# Blinky_Schematic.net
KiCad netlist of a schematic drawn in EAGLE
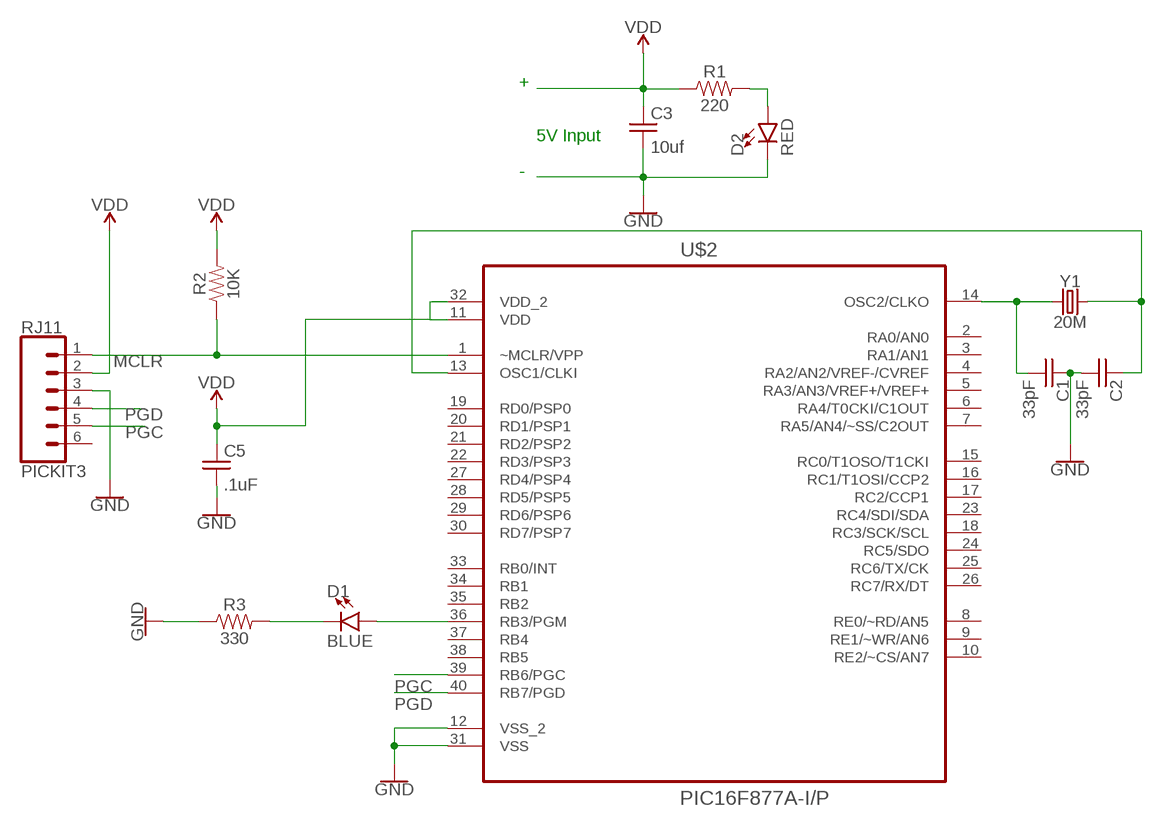
[diagram p0: schematic, sheet 1]

(export (version "E")
  (design (tool "Eeschema 10.0.6"))
  (components
    (comp (ref "C1")
      (value "33pF")
      (footprint "eagle-import:CAP_BULK")
      (fields (field (name "PARTNO") "EEE-FK1H220P"))
      (libsource (lib "eagle-import") (part "CAP_22UF_50VCAP_22UF_50V"))
    )
    (comp (ref "C2")
      (value "33pF")
      (footprint "eagle-import:CAP_BULK")
      (fields (field (name "PARTNO") "EEE-FK1H220P"))
      (libsource (lib "eagle-import") (part "CAP_22UF_50VCAP_22UF_50V"))
    )
    (comp (ref "C3")
      (value "10uf")
      (footprint "eagle-import:CAP_BULK")
      (fields (field (name "PARTNO") "EEE-FK1H220P"))
      (libsource (lib "eagle-import") (part "CAP_22UF_50VCAP_22UF_50V"))
    )
    (comp (ref "C5")
      (value ".1uF")
      (footprint "eagle-import:CAP_BULK")
      (fields (field (name "PARTNO") "EEE-FK1H220P"))
      (libsource (lib "eagle-import") (part "CAP_22UF_50VCAP_22UF_50V"))
    )
    (comp (ref "D1")
      (value "BLUE")
      (footprint "eagle-import:LED-0603")
      (libsource (lib "eagle-import") (part "LED-BLUE0603"))
    )
    (comp (ref "D2")
      (value "RED")
      (footprint "eagle-import:LED-0603")
      (libsource (lib "eagle-import") (part "LED-RED0603"))
    )
    (comp (ref "PICKIT3")
      (value "RJ11")
      (footprint "eagle-import:RJ11-6")
      (libsource (lib "eagle-import") (part "RJ11-6"))
    )
    (comp (ref "R1")
      (value "220")
      (footprint "eagle-import:0603")
      (libsource (lib "eagle-import") (part "1.2MOHM-0603-1/10W-1%"))
    )
    (comp (ref "R2")
      (value "10K")
      (footprint "eagle-import:0603")
      (libsource (lib "eagle-import") (part "1.2MOHM-0603-1/10W-1%"))
    )
    (comp (ref "R3")
      (value "330")
      (footprint "eagle-import:0603")
      (libsource (lib "eagle-import") (part "1.2MOHM-0603-1/10W-1%"))
    )
    (comp (ref "U$2")
      (value "PIC16F877A-I/P")
      (footprint "eagle-import:DIP254P1524X483-40")
      (libsource (lib "eagle-import") (part "PIC16F877A-I/P"))
    )
    (comp (ref "Y1")
      (value "20M")
      (footprint "eagle-import:CRYSTAL-PTH-2X6-CYL")
      (libsource (lib "eagle-import") (part "CRYSTALPTH-2X6"))
    )
  )
  (nets
    (net (code "1") (name "/MCLR") (class "Default")
      (node (ref "PICKIT3") (pin "1") (pinfunction "1_1") (pintype "passive"))
      (node (ref "R2") (pin "1") (pinfunction "1_1") (pintype "passive"))
      (node (ref "U$2") (pin "1") (pinfunction "~{MCLR/VPP}_1") (pintype "input"))
    )
    (net (code "2") (name "/PGC") (class "Default")
      (node (ref "PICKIT3") (pin "5") (pinfunction "5_5") (pintype "passive"))
      (node (ref "U$2") (pin "39") (pinfunction "RB6/PGC_39") (pintype "bidirectional"))
    )
    (net (code "3") (name "/PGD") (class "Default")
      (node (ref "PICKIT3") (pin "4") (pinfunction "4_4") (pintype "passive"))
      (node (ref "U$2") (pin "40") (pinfunction "RB7/PGD_40") (pintype "bidirectional"))
    )
    (net (code "4") (name "GND") (class "Default")
      (node (ref "C1") (pin "A") (pinfunction "+_A") (pintype "passive"))
      (node (ref "C2") (pin "B") (pinfunction "-_B") (pintype "passive"))
      (node (ref "C3") (pin "B") (pinfunction "-_B") (pintype "passive"))
      (node (ref "C5") (pin "B") (pinfunction "-_B") (pintype "passive"))
      (node (ref "D2") (pin "C") (pinfunction "C_C") (pintype "passive"))
      (node (ref "PICKIT3") (pin "3") (pinfunction "3_3") (pintype "passive"))
      (node (ref "R3") (pin "1") (pinfunction "1_1") (pintype "passive"))
      (node (ref "U$2") (pin "12") (pinfunction "VSS_2_12") (pintype "power_in"))
      (node (ref "U$2") (pin "31") (pinfunction "VSS_31") (pintype "power_in"))
    )
    (net (code "5") (name "Net-(C1--)") (class "Default")
      (node (ref "C1") (pin "B") (pinfunction "-_B") (pintype "passive"))
      (node (ref "U$2") (pin "14") (pinfunction "OSC2/CLKO_14") (pintype "output"))
      (node (ref "Y1") (pin "1") (pinfunction "1_1") (pintype "passive"))
    )
    (net (code "6") (name "Net-(C2-+)") (class "Default")
      (node (ref "C2") (pin "A") (pinfunction "+_A") (pintype "passive"))
      (node (ref "U$2") (pin "13") (pinfunction "OSC1/CLKI_13") (pintype "input"))
      (node (ref "Y1") (pin "2") (pinfunction "2_2") (pintype "passive"))
    )
    (net (code "7") (name "Net-(D1-PadC)") (class "Default")
      (node (ref "D1") (pin "C") (pinfunction "C_C") (pintype "passive"))
      (node (ref "R3") (pin "2") (pinfunction "2_2") (pintype "passive"))
    )
    (net (code "8") (name "Net-(D2-PadA)") (class "Default")
      (node (ref "D2") (pin "A") (pinfunction "A_A") (pintype "passive"))
      (node (ref "R1") (pin "2") (pinfunction "2_2") (pintype "passive"))
    )
    (net (code "9") (name "Net-(U$2-RB3{slash}PGM)") (class "Default")
      (node (ref "D1") (pin "A") (pinfunction "A_A") (pintype "passive"))
      (node (ref "U$2") (pin "36") (pinfunction "RB3/PGM_36") (pintype "bidirectional"))
    )
    (net (code "10") (name "VDD") (class "Default")
      (node (ref "C3") (pin "A") (pinfunction "+_A") (pintype "passive"))
      (node (ref "C5") (pin "A") (pinfunction "+_A") (pintype "passive"))
      (node (ref "PICKIT3") (pin "2") (pinfunction "2_2") (pintype "passive"))
      (node (ref "R1") (pin "1") (pinfunction "1_1") (pintype "passive"))
      (node (ref "R2") (pin "2") (pinfunction "2_2") (pintype "passive"))
      (node (ref "U$2") (pin "11") (pinfunction "VDD_11") (pintype "power_in"))
      (node (ref "U$2") (pin "32") (pinfunction "VDD_2_32") (pintype "power_in"))
    )
    (net (code "11") (name "unconnected-(PICKIT3-Pad6)") (class "Default")
      (node (ref "PICKIT3") (pin "6") (pinfunction "6_6") (pintype "passive"))
    )
    (net (code "12") (name "unconnected-(U$2-RA0{slash}AN0-Pad2)") (class "Default")
      (node (ref "U$2") (pin "2") (pinfunction "RA0/AN0_2") (pintype "bidirectional"))
    )
    (net (code "13") (name "unconnected-(U$2-RA1{slash}AN1-Pad3)") (class "Default")
      (node (ref "U$2") (pin "3") (pinfunction "RA1/AN1_3") (pintype "bidirectional"))
    )
    (net (code "14") (name "unconnected-(U$2-RA2{slash}AN2{slash}VREF-{slash}CVREF-Pad4)") (class "Default")
      (node (ref "U$2") (pin "4") (pinfunction "RA2/AN2/VREF-/CVREF_4") (pintype "bidirectional"))
    )
    (net (code "15") (name "unconnected-(U$2-RA3{slash}AN3{slash}VREF+{slash}VREF+-Pad5)") (class "Default")
      (node (ref "U$2") (pin "5") (pinfunction "RA3/AN3/VREF+/VREF+_5") (pintype "bidirectional"))
    )
    (net (code "16") (name "unconnected-(U$2-RA4{slash}T0CKI{slash}C1OUT-Pad6)") (class "Default")
      (node (ref "U$2") (pin "6") (pinfunction "RA4/T0CKI/C1OUT_6") (pintype "bidirectional"))
    )
    (net (code "17") (name "unconnected-(U$2-RA5{slash}AN4{slash}~{SS{slash}C2OUT}-Pad7)") (class "Default")
      (node (ref "U$2") (pin "7") (pinfunction "RA5/AN4/~{SS/C2OUT}_7") (pintype "bidirectional"))
    )
    (net (code "18") (name "unconnected-(U$2-RB0{slash}INT-Pad33)") (class "Default")
      (node (ref "U$2") (pin "33") (pinfunction "RB0/INT_33") (pintype "bidirectional"))
    )
    (net (code "19") (name "unconnected-(U$2-RB1-Pad34)") (class "Default")
      (node (ref "U$2") (pin "34") (pinfunction "RB1_34") (pintype "bidirectional"))
    )
    (net (code "20") (name "unconnected-(U$2-RB2-Pad35)") (class "Default")
      (node (ref "U$2") (pin "35") (pinfunction "RB2_35") (pintype "bidirectional"))
    )
    (net (code "21") (name "unconnected-(U$2-RB4-Pad37)") (class "Default")
      (node (ref "U$2") (pin "37") (pinfunction "RB4_37") (pintype "bidirectional"))
    )
    (net (code "22") (name "unconnected-(U$2-RB5-Pad38)") (class "Default")
      (node (ref "U$2") (pin "38") (pinfunction "RB5_38") (pintype "bidirectional"))
    )
    (net (code "23") (name "unconnected-(U$2-RC0{slash}T1OSO{slash}T1CKI-Pad15)") (class "Default")
      (node (ref "U$2") (pin "15") (pinfunction "RC0/T1OSO/T1CKI_15") (pintype "bidirectional"))
    )
    (net (code "24") (name "unconnected-(U$2-RC1{slash}T1OSI{slash}CCP2-Pad16)") (class "Default")
      (node (ref "U$2") (pin "16") (pinfunction "RC1/T1OSI/CCP2_16") (pintype "bidirectional"))
    )
    (net (code "25") (name "unconnected-(U$2-RC2{slash}CCP1-Pad17)") (class "Default")
      (node (ref "U$2") (pin "17") (pinfunction "RC2/CCP1_17") (pintype "bidirectional"))
    )
    (net (code "26") (name "unconnected-(U$2-RC3{slash}SCK{slash}SCL-Pad18)") (class "Default")
      (node (ref "U$2") (pin "18") (pinfunction "RC3/SCK/SCL_18") (pintype "bidirectional"))
    )
    (net (code "27") (name "unconnected-(U$2-RC4{slash}SDI{slash}SDA-Pad23)") (class "Default")
      (node (ref "U$2") (pin "23") (pinfunction "RC4/SDI/SDA_23") (pintype "bidirectional"))
    )
    (net (code "28") (name "unconnected-(U$2-RC5{slash}SDO-Pad24)") (class "Default")
      (node (ref "U$2") (pin "24") (pinfunction "RC5/SDO_24") (pintype "bidirectional"))
    )
    (net (code "29") (name "unconnected-(U$2-RC6{slash}TX{slash}CK-Pad25)") (class "Default")
      (node (ref "U$2") (pin "25") (pinfunction "RC6/TX/CK_25") (pintype "bidirectional"))
    )
    (net (code "30") (name "unconnected-(U$2-RC7{slash}RX{slash}DT-Pad26)") (class "Default")
      (node (ref "U$2") (pin "26") (pinfunction "RC7/RX/DT_26") (pintype "bidirectional"))
    )
    (net (code "31") (name "unconnected-(U$2-RD0{slash}PSP0-Pad19)") (class "Default")
      (node (ref "U$2") (pin "19") (pinfunction "RD0/PSP0_19") (pintype "bidirectional"))
    )
    (net (code "32") (name "unconnected-(U$2-RD1{slash}PSP1-Pad20)") (class "Default")
      (node (ref "U$2") (pin "20") (pinfunction "RD1/PSP1_20") (pintype "bidirectional"))
    )
    (net (code "33") (name "unconnected-(U$2-RD2{slash}PSP2-Pad21)") (class "Default")
      (node (ref "U$2") (pin "21") (pinfunction "RD2/PSP2_21") (pintype "bidirectional"))
    )
    (net (code "34") (name "unconnected-(U$2-RD3{slash}PSP3-Pad22)") (class "Default")
      (node (ref "U$2") (pin "22") (pinfunction "RD3/PSP3_22") (pintype "bidirectional"))
    )
    (net (code "35") (name "unconnected-(U$2-RD4{slash}PSP4-Pad27)") (class "Default")
      (node (ref "U$2") (pin "27") (pinfunction "RD4/PSP4_27") (pintype "bidirectional"))
    )
    (net (code "36") (name "unconnected-(U$2-RD5{slash}PSP5-Pad28)") (class "Default")
      (node (ref "U$2") (pin "28") (pinfunction "RD5/PSP5_28") (pintype "bidirectional"))
    )
    (net (code "37") (name "unconnected-(U$2-RD6{slash}PSP6-Pad29)") (class "Default")
      (node (ref "U$2") (pin "29") (pinfunction "RD6/PSP6_29") (pintype "bidirectional"))
    )
    (net (code "38") (name "unconnected-(U$2-RD7{slash}PSP7-Pad30)") (class "Default")
      (node (ref "U$2") (pin "30") (pinfunction "RD7/PSP7_30") (pintype "bidirectional"))
    )
    (net (code "39") (name "unconnected-(U$2-RE0{slash}~{RD{slash}AN5}-Pad8)") (class "Default")
      (node (ref "U$2") (pin "8") (pinfunction "RE0/~{RD/AN5}_8") (pintype "bidirectional"))
    )
    (net (code "40") (name "unconnected-(U$2-RE1{slash}~{WR{slash}AN6}-Pad9)") (class "Default")
      (node (ref "U$2") (pin "9") (pinfunction "RE1/~{WR/AN6}_9") (pintype "bidirectional"))
    )
    (net (code "41") (name "unconnected-(U$2-RE2{slash}~{CS{slash}AN7}-Pad10)") (class "Default")
      (node (ref "U$2") (pin "10") (pinfunction "RE2/~{CS/AN7}_10") (pintype "bidirectional"))
    )
  )
)
